# LCD_Board_v1_3.net
KiCad netlist of a schematic drawn in EAGLE
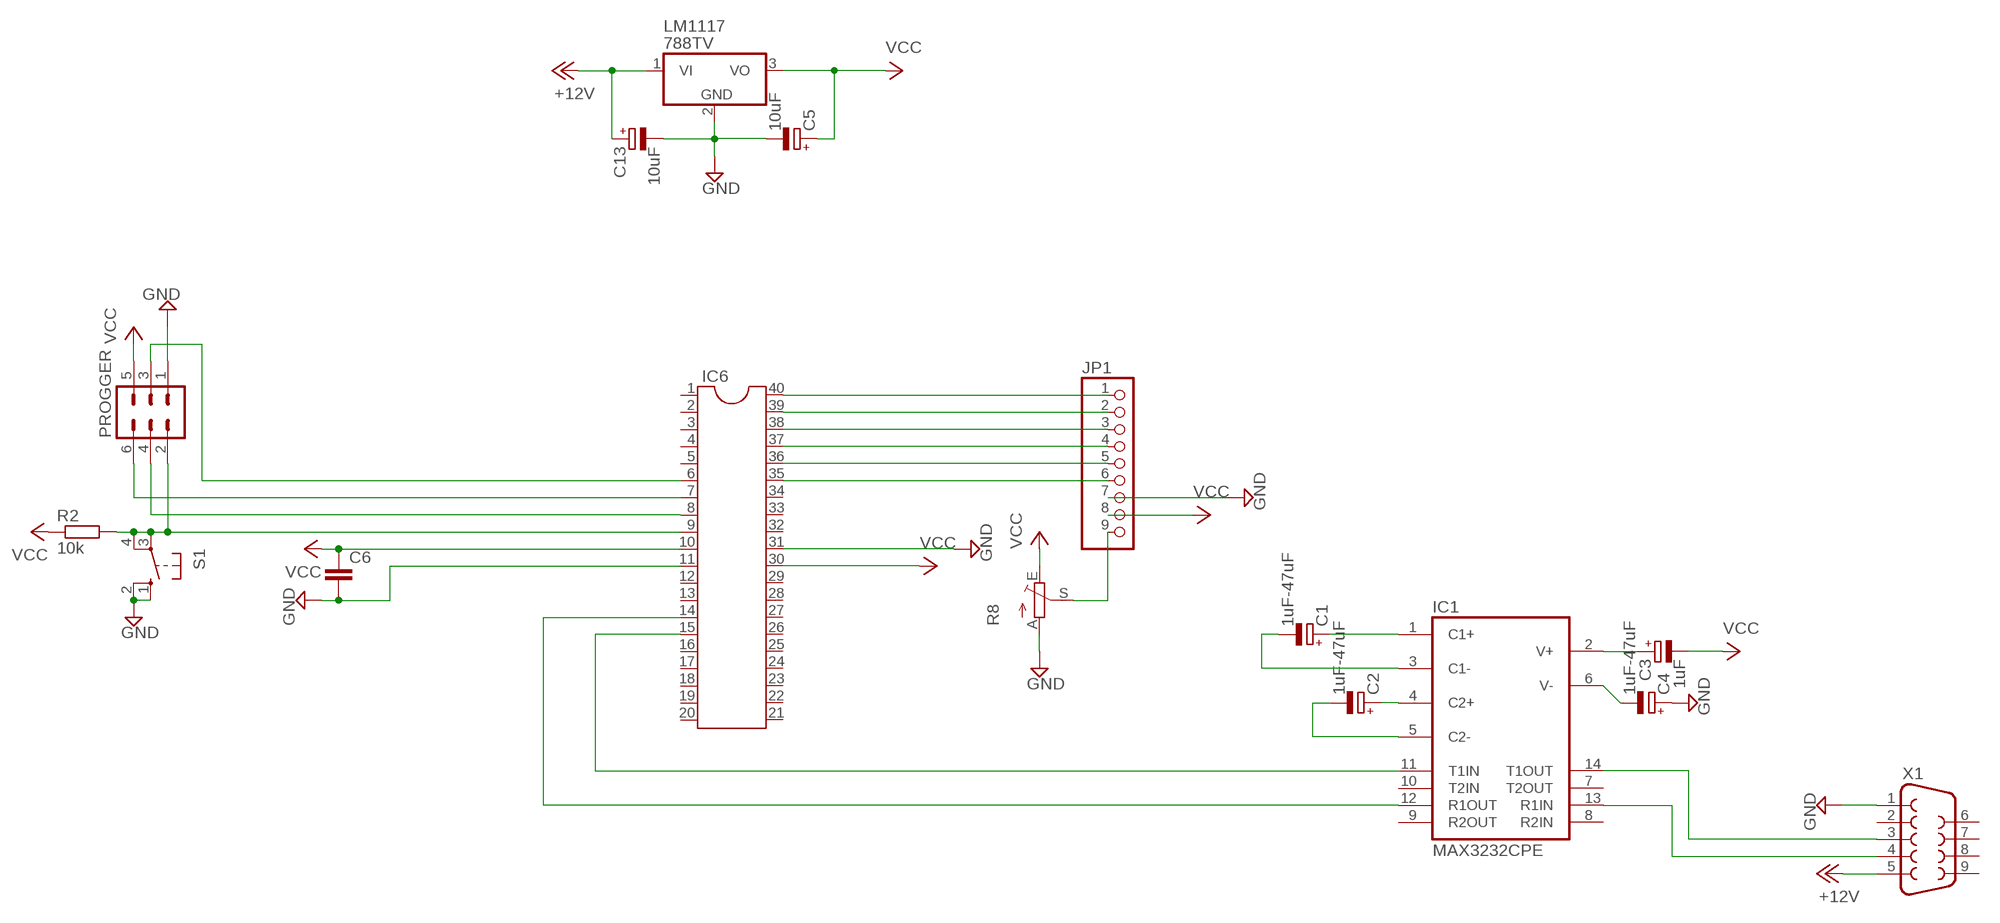
[diagram p0: schematic, sheet 1]
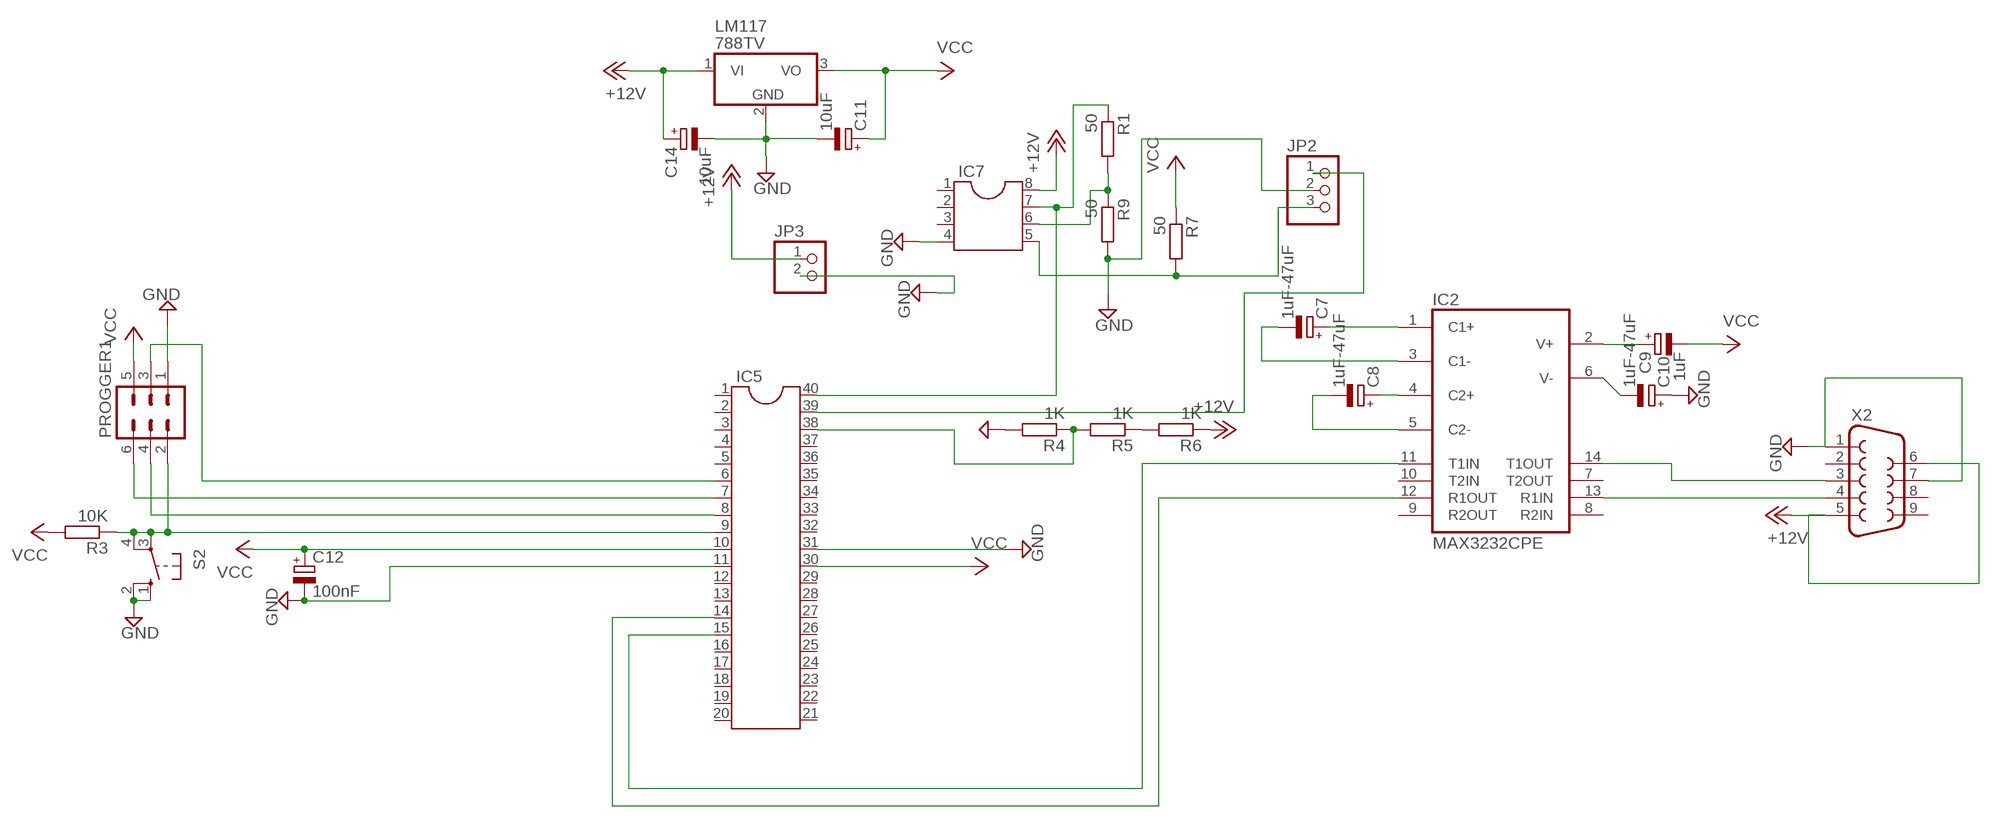
[diagram p1: schematic, sheet 2]

(export (version "E")
  (design (tool "Eeschema 10.0.6"))
  (components
    (comp (ref "C7")
      (value "1uF-47uF")
      (footprint "eagle-import:TT5D7")
      (libsource (lib "eagle-import") (part "CPOL-EUTT5D7"))
    )
    (comp (ref "C8")
      (value "1uF-47uF")
      (footprint "eagle-import:E2,5RE")
      (libsource (lib "eagle-import") (part "CPOL-EUE2.5-4V"))
    )
    (comp (ref "C9")
      (value "1uF")
      (footprint "eagle-import:TT5D7")
      (libsource (lib "eagle-import") (part "CPOL-EUTT5D7"))
    )
    (comp (ref "C10")
      (value "1uF-47uF")
      (footprint "eagle-import:E2,5RE")
      (libsource (lib "eagle-import") (part "CPOL-EUE2.5-4V"))
    )
    (comp (ref "C11")
      (value "10uF")
      (footprint "eagle-import:E2,5RE")
      (libsource (lib "eagle-import") (part "CPOL-EUE2.5-4V"))
    )
    (comp (ref "C12")
      (value "100nF")
      (footprint "eagle-import:E2,5RE")
      (libsource (lib "eagle-import") (part "CPOL-EUE2.5-4V"))
    )
    (comp (ref "C14")
      (value "10uF")
      (footprint "eagle-import:E2,5RE")
      (libsource (lib "eagle-import") (part "CPOL-EUE2.5-4V"))
    )
    (comp (ref "IC2")
      (value "MAX3232CPE")
      (footprint "eagle-import:DIL16")
      (fields (field (name "MF") "MAXIM") (field (name "MPN") "MAX3232CPE+"))
      (libsource (lib "eagle-import") (part "MAX3232PEC"))
    )
    (comp (ref "IC5")
      (value "DIL40")
      (footprint "eagle-import:DIL40")
      (libsource (lib "eagle-import") (part "DIL40"))
    )
    (comp (ref "IC7")
      (value "DIL8")
      (footprint "eagle-import:DIL08")
      (libsource (lib "eagle-import") (part "DIL8"))
    )
    (comp (ref "JP2")
      (value "PINHD-1X3")
      (footprint "eagle-import:1X03")
      (libsource (lib "eagle-import") (part "PINHD-1X3"))
    )
    (comp (ref "JP3")
      (value "PINHD-1X2")
      (footprint "eagle-import:1X02")
      (libsource (lib "eagle-import") (part "PINHD-1X2"))
    )
    (comp (ref "LM117")
      (value "788TV")
      (footprint "eagle-import:TO220V")
      (libsource (lib "eagle-import") (part "78TV8"))
    )
    (comp (ref "PROGGER1")
      (value "MA03-2")
      (footprint "eagle-import:MA03-2")
      (libsource (lib "eagle-import") (part "MA03-2"))
    )
    (comp (ref "R1")
      (value "50")
      (footprint "eagle-import:0204_7")
      (libsource (lib "eagle-import") (part "R-EU_0204/7"))
    )
    (comp (ref "R3")
      (value "10K")
      (footprint "eagle-import:0207_7")
      (libsource (lib "eagle-import") (part "R-EU_0207/7"))
    )
    (comp (ref "R4")
      (value "1K")
      (footprint "eagle-import:0204_7")
      (libsource (lib "eagle-import") (part "resistor_R-EU_0204/7"))
    )
    (comp (ref "R5")
      (value "1K")
      (footprint "eagle-import:0204_7")
      (libsource (lib "eagle-import") (part "resistor_R-EU_0204/7"))
    )
    (comp (ref "R6")
      (value "1K")
      (footprint "eagle-import:0204_7")
      (libsource (lib "eagle-import") (part "resistor_R-EU_0204/7"))
    )
    (comp (ref "R7")
      (value "50")
      (footprint "eagle-import:0204_5")
      (libsource (lib "eagle-import") (part "resistor_R-EU_0204/5"))
    )
    (comp (ref "R9")
      (value "50")
      (footprint "eagle-import:0204_7")
      (libsource (lib "eagle-import") (part "R-EU_0204/7"))
    )
    (comp (ref "S2")
      (value "10-XX")
      (footprint "eagle-import:B3F-10XX")
      (fields (field (name "MPN") "B3F-1000"))
      (libsource (lib "eagle-import") (part "10-XX"))
    )
    (comp (ref "X2")
      (value "F09H")
      (footprint "eagle-import:F09H")
      (libsource (lib "eagle-import") (part "F09H"))
    )
    (comp (ref "C1")
      (value "1uF-47uF")
      (footprint "eagle-import:TT5D7")
      (libsource (lib "eagle-import") (part "CPOL-EUTT5D7"))
    )
    (comp (ref "C2")
      (value "1uF-47uF")
      (footprint "eagle-import:E2,5RE")
      (libsource (lib "eagle-import") (part "CPOL-EUE2.5-4V"))
    )
    (comp (ref "C3")
      (value "1uF")
      (footprint "eagle-import:TT5D7")
      (libsource (lib "eagle-import") (part "CPOL-EUTT5D7"))
    )
    (comp (ref "C4")
      (value "1uF-47uF")
      (footprint "eagle-import:E2,5RE")
      (libsource (lib "eagle-import") (part "CPOL-EUE2.5-4V"))
    )
    (comp (ref "C5")
      (value "10uF")
      (footprint "eagle-import:E3,5-8")
      (libsource (lib "eagle-import") (part "CPOL-EUE3.5-8"))
    )
    (comp (ref "C6")
      (value "C-EU025-030X050")
      (footprint "eagle-import:C025-030X050")
      (libsource (lib "eagle-import") (part "C-EU025-030X050"))
    )
    (comp (ref "C13")
      (value "10uF")
      (footprint "eagle-import:E2,5RE")
      (libsource (lib "eagle-import") (part "CPOL-EUE2.5-4V"))
    )
    (comp (ref "IC1")
      (value "MAX3232CPE")
      (footprint "eagle-import:DIL16")
      (fields (field (name "MF") "MAXIM") (field (name "MPN") "MAX3232CPE+"))
      (libsource (lib "eagle-import") (part "MAX3232PEC"))
    )
    (comp (ref "IC6")
      (value "DIL40")
      (footprint "eagle-import:DIL40")
      (libsource (lib "eagle-import") (part "DIL40"))
    )
    (comp (ref "JP1")
      (value "PINHD-1X9")
      (footprint "eagle-import:1X09")
      (libsource (lib "eagle-import") (part "PINHD-1X9"))
    )
    (comp (ref "LM1117")
      (value "788TV")
      (footprint "eagle-import:TO220V")
      (libsource (lib "eagle-import") (part "78TV8"))
    )
    (comp (ref "PROGGER")
      (value "MA03-2")
      (footprint "eagle-import:MA03-2")
      (libsource (lib "eagle-import") (part "MA03-2"))
    )
    (comp (ref "R2")
      (value "10k")
      (footprint "eagle-import:0207_7")
      (libsource (lib "eagle-import") (part "R-EU_0207/7"))
    )
    (comp (ref "R8")
      (value "TRIM_EU-CA6V")
      (footprint "eagle-import:CA6V")
      (libsource (lib "eagle-import") (part "TRIM_EU-CA6V"))
    )
    (comp (ref "S1")
      (value "10-XX")
      (footprint "eagle-import:B3F-10XX")
      (fields (field (name "MPN") "B3F-1000"))
      (libsource (lib "eagle-import") (part "10-XX"))
    )
    (comp (ref "X1")
      (value "F09H")
      (footprint "eagle-import:F09H")
      (libsource (lib "eagle-import") (part "F09H"))
    )
  )
  (nets
    (net (code "1") (name "$N4") (class "Default")
      (node (ref "C10") (pin "+") (pinfunction "+_+") (pintype "passive"))
      (node (ref "C11") (pin "-") (pinfunction "-_-") (pintype "passive"))
      (node (ref "C12") (pin "-") (pinfunction "-_-") (pintype "passive"))
      (node (ref "C13") (pin "-") (pinfunction "-_-") (pintype "passive"))
      (node (ref "C14") (pin "-") (pinfunction "-_-") (pintype "passive"))
      (node (ref "C4") (pin "+") (pinfunction "+_+") (pintype "passive"))
      (node (ref "C5") (pin "-") (pinfunction "-_-") (pintype "passive"))
      (node (ref "C6") (pin "2") (pinfunction "2_2") (pintype "passive"))
      (node (ref "IC5") (pin "11") (pinfunction "11_11") (pintype "passive"))
      (node (ref "IC5") (pin "31") (pinfunction "31_31") (pintype "passive"))
      (node (ref "IC6") (pin "11") (pinfunction "11_11") (pintype "passive"))
      (node (ref "IC6") (pin "31") (pinfunction "31_31") (pintype "passive"))
      (node (ref "IC7") (pin "4") (pinfunction "4_4") (pintype "passive"))
      (node (ref "JP1") (pin "7") (pinfunction "7_7") (pintype "passive"))
      (node (ref "JP2") (pin "2") (pinfunction "2_2") (pintype "passive"))
      (node (ref "JP3") (pin "2") (pinfunction "2_2") (pintype "passive"))
      (node (ref "LM1117") (pin "2") (pinfunction "GND_2") (pintype "passive"))
      (node (ref "LM117") (pin "2") (pinfunction "GND_2") (pintype "passive"))
      (node (ref "PROGGER") (pin "1") (pinfunction "1_1") (pintype "passive"))
      (node (ref "PROGGER1") (pin "1") (pinfunction "1_1") (pintype "passive"))
      (node (ref "R4") (pin "2") (pinfunction "2_2") (pintype "passive"))
      (node (ref "R8") (pin "A") (pinfunction "A_A") (pintype "passive"))
      (node (ref "R9") (pin "2") (pinfunction "2_2") (pintype "passive"))
      (node (ref "S1") (pin "1") (pinfunction "S_1") (pintype "passive"))
      (node (ref "S1") (pin "2") (pinfunction "S1_2") (pintype "passive"))
      (node (ref "S2") (pin "1") (pinfunction "S_1") (pintype "passive"))
      (node (ref "S2") (pin "2") (pinfunction "S1_2") (pintype "passive"))
      (node (ref "X1") (pin "1") (pinfunction "1_1") (pintype "passive"))
      (node (ref "X2") (pin "1") (pinfunction "1_1") (pintype "passive"))
      (node (ref "X2") (pin "7") (pinfunction "7_7") (pintype "passive"))
    )
    (net (code "2") (name "+12V") (class "Default")
      (node (ref "C13") (pin "+") (pinfunction "+_+") (pintype "passive"))
      (node (ref "C14") (pin "+") (pinfunction "+_+") (pintype "passive"))
      (node (ref "IC7") (pin "8") (pinfunction "8_8") (pintype "passive"))
      (node (ref "JP3") (pin "1") (pinfunction "1_1") (pintype "passive"))
      (node (ref "LM1117") (pin "1") (pinfunction "VI_1") (pintype "input"))
      (node (ref "LM117") (pin "1") (pinfunction "VI_1") (pintype "input"))
      (node (ref "R6") (pin "1") (pinfunction "1_1") (pintype "passive"))
      (node (ref "X1") (pin "5") (pinfunction "5_5") (pintype "passive"))
      (node (ref "X2") (pin "5") (pinfunction "5_5") (pintype "passive"))
      (node (ref "X2") (pin "6") (pinfunction "6_6") (pintype "passive"))
    )
    (net (code "3") (name "Net-(IC1A-C1+)") (class "Default")
      (node (ref "C1") (pin "+") (pinfunction "+_+") (pintype "passive"))
      (node (ref "IC1") (pin "1") (pinfunction "C1+_1") (pintype "bidirectional"))
    )
    (net (code "4") (name "Net-(IC1A-C1-)") (class "Default")
      (node (ref "C1") (pin "-") (pinfunction "-_-") (pintype "passive"))
      (node (ref "IC1") (pin "3") (pinfunction "C1-_3") (pintype "bidirectional"))
    )
    (net (code "5") (name "Net-(IC1A-C2+)") (class "Default")
      (node (ref "C2") (pin "+") (pinfunction "+_+") (pintype "passive"))
      (node (ref "IC1") (pin "4") (pinfunction "C2+_4") (pintype "bidirectional"))
    )
    (net (code "6") (name "Net-(IC1A-C2-)") (class "Default")
      (node (ref "C2") (pin "-") (pinfunction "-_-") (pintype "passive"))
      (node (ref "IC1") (pin "5") (pinfunction "C2-_5") (pintype "bidirectional"))
    )
    (net (code "7") (name "Net-(IC1A-R1IN)") (class "Default")
      (node (ref "IC1") (pin "13") (pinfunction "R1IN_13") (pintype "input"))
      (node (ref "X1") (pin "4") (pinfunction "4_4") (pintype "passive"))
    )
    (net (code "8") (name "Net-(IC1A-R1OUT)") (class "Default")
      (node (ref "IC1") (pin "12") (pinfunction "R1OUT_12") (pintype "output"))
      (node (ref "IC6") (pin "14") (pinfunction "14_14") (pintype "passive"))
    )
    (net (code "9") (name "Net-(IC1A-T1IN)") (class "Default")
      (node (ref "IC1") (pin "11") (pinfunction "T1IN_11") (pintype "input"))
      (node (ref "IC6") (pin "15") (pinfunction "15_15") (pintype "passive"))
    )
    (net (code "10") (name "Net-(IC1A-T1OUT)") (class "Default")
      (node (ref "IC1") (pin "14") (pinfunction "T1OUT_14") (pintype "output"))
      (node (ref "X1") (pin "3") (pinfunction "3_3") (pintype "passive"))
    )
    (net (code "11") (name "Net-(IC1A-V+)") (class "Default")
      (node (ref "C3") (pin "+") (pinfunction "+_+") (pintype "passive"))
      (node (ref "IC1") (pin "2") (pinfunction "V+_2") (pintype "bidirectional"))
    )
    (net (code "12") (name "Net-(IC1A-V-)") (class "Default")
      (node (ref "C4") (pin "-") (pinfunction "-_-") (pintype "passive"))
      (node (ref "IC1") (pin "6") (pinfunction "V-_6") (pintype "bidirectional"))
    )
    (net (code "13") (name "Net-(IC2A-C1+)") (class "Default")
      (node (ref "C7") (pin "+") (pinfunction "+_+") (pintype "passive"))
      (node (ref "IC2") (pin "1") (pinfunction "C1+_1") (pintype "bidirectional"))
    )
    (net (code "14") (name "Net-(IC2A-C1-)") (class "Default")
      (node (ref "C7") (pin "-") (pinfunction "-_-") (pintype "passive"))
      (node (ref "IC2") (pin "3") (pinfunction "C1-_3") (pintype "bidirectional"))
    )
    (net (code "15") (name "Net-(IC2A-C2+)") (class "Default")
      (node (ref "C8") (pin "+") (pinfunction "+_+") (pintype "passive"))
      (node (ref "IC2") (pin "4") (pinfunction "C2+_4") (pintype "bidirectional"))
    )
    (net (code "16") (name "Net-(IC2A-C2-)") (class "Default")
      (node (ref "C8") (pin "-") (pinfunction "-_-") (pintype "passive"))
      (node (ref "IC2") (pin "5") (pinfunction "C2-_5") (pintype "bidirectional"))
    )
    (net (code "17") (name "Net-(IC2A-R1IN)") (class "Default")
      (node (ref "IC2") (pin "13") (pinfunction "R1IN_13") (pintype "input"))
      (node (ref "X2") (pin "4") (pinfunction "4_4") (pintype "passive"))
    )
    (net (code "18") (name "Net-(IC2A-R1OUT)") (class "Default")
      (node (ref "IC2") (pin "12") (pinfunction "R1OUT_12") (pintype "output"))
      (node (ref "IC5") (pin "14") (pinfunction "14_14") (pintype "passive"))
    )
    (net (code "19") (name "Net-(IC2A-T1IN)") (class "Default")
      (node (ref "IC2") (pin "11") (pinfunction "T1IN_11") (pintype "input"))
      (node (ref "IC5") (pin "15") (pinfunction "15_15") (pintype "passive"))
    )
    (net (code "20") (name "Net-(IC2A-T1OUT)") (class "Default")
      (node (ref "IC2") (pin "14") (pinfunction "T1OUT_14") (pintype "output"))
      (node (ref "X2") (pin "3") (pinfunction "3_3") (pintype "passive"))
    )
    (net (code "21") (name "Net-(IC2A-V+)") (class "Default")
      (node (ref "C9") (pin "+") (pinfunction "+_+") (pintype "passive"))
      (node (ref "IC2") (pin "2") (pinfunction "V+_2") (pintype "bidirectional"))
    )
    (net (code "22") (name "Net-(IC2A-V-)") (class "Default")
      (node (ref "C10") (pin "-") (pinfunction "-_-") (pintype "passive"))
      (node (ref "IC2") (pin "6") (pinfunction "V-_6") (pintype "bidirectional"))
    )
    (net (code "23") (name "Net-(IC5-Pad6)") (class "Default")
      (node (ref "IC5") (pin "6") (pinfunction "6_6") (pintype "passive"))
      (node (ref "PROGGER1") (pin "3") (pinfunction "3_3") (pintype "passive"))
    )
    (net (code "24") (name "Net-(IC5-Pad7)") (class "Default")
      (node (ref "IC5") (pin "7") (pinfunction "7_7") (pintype "passive"))
      (node (ref "PROGGER1") (pin "6") (pinfunction "6_6") (pintype "passive"))
    )
    (net (code "25") (name "Net-(IC5-Pad8)") (class "Default")
      (node (ref "IC5") (pin "8") (pinfunction "8_8") (pintype "passive"))
      (node (ref "PROGGER1") (pin "4") (pinfunction "4_4") (pintype "passive"))
    )
    (net (code "26") (name "Net-(IC5-Pad38)") (class "Default")
      (node (ref "IC5") (pin "38") (pinfunction "38_38") (pintype "passive"))
      (node (ref "R4") (pin "1") (pinfunction "1_1") (pintype "passive"))
      (node (ref "R5") (pin "2") (pinfunction "2_2") (pintype "passive"))
    )
    (net (code "27") (name "Net-(IC5-Pad39)") (class "Default")
      (node (ref "IC5") (pin "39") (pinfunction "39_39") (pintype "passive"))
      (node (ref "JP2") (pin "1") (pinfunction "1_1") (pintype "passive"))
    )
    (net (code "28") (name "Net-(IC5-Pad40)") (class "Default")
      (node (ref "IC5") (pin "40") (pinfunction "40_40") (pintype "passive"))
      (node (ref "IC7") (pin "7") (pinfunction "7_7") (pintype "passive"))
      (node (ref "R1") (pin "1") (pinfunction "1_1") (pintype "passive"))
    )
    (net (code "29") (name "Net-(IC6-Pad6)") (class "Default")
      (node (ref "IC6") (pin "6") (pinfunction "6_6") (pintype "passive"))
      (node (ref "PROGGER") (pin "3") (pinfunction "3_3") (pintype "passive"))
    )
    (net (code "30") (name "Net-(IC6-Pad7)") (class "Default")
      (node (ref "IC6") (pin "7") (pinfunction "7_7") (pintype "passive"))
      (node (ref "PROGGER") (pin "6") (pinfunction "6_6") (pintype "passive"))
    )
    (net (code "31") (name "Net-(IC6-Pad8)") (class "Default")
      (node (ref "IC6") (pin "8") (pinfunction "8_8") (pintype "passive"))
      (node (ref "PROGGER") (pin "4") (pinfunction "4_4") (pintype "passive"))
    )
    (net (code "32") (name "Net-(IC6-Pad35)") (class "Default")
      (node (ref "IC6") (pin "35") (pinfunction "35_35") (pintype "passive"))
      (node (ref "JP1") (pin "6") (pinfunction "6_6") (pintype "passive"))
    )
    (net (code "33") (name "Net-(IC6-Pad36)") (class "Default")
      (node (ref "IC6") (pin "36") (pinfunction "36_36") (pintype "passive"))
      (node (ref "JP1") (pin "5") (pinfunction "5_5") (pintype "passive"))
    )
    (net (code "34") (name "Net-(IC6-Pad37)") (class "Default")
      (node (ref "IC6") (pin "37") (pinfunction "37_37") (pintype "passive"))
      (node (ref "JP1") (pin "4") (pinfunction "4_4") (pintype "passive"))
    )
    (net (code "35") (name "Net-(IC6-Pad38)") (class "Default")
      (node (ref "IC6") (pin "38") (pinfunction "38_38") (pintype "passive"))
      (node (ref "JP1") (pin "3") (pinfunction "3_3") (pintype "passive"))
    )
    (net (code "36") (name "Net-(IC6-Pad39)") (class "Default")
      (node (ref "IC6") (pin "39") (pinfunction "39_39") (pintype "passive"))
      (node (ref "JP1") (pin "2") (pinfunction "2_2") (pintype "passive"))
    )
    (net (code "37") (name "Net-(IC6-Pad40)") (class "Default")
      (node (ref "IC6") (pin "40") (pinfunction "40_40") (pintype "passive"))
      (node (ref "JP1") (pin "1") (pinfunction "1_1") (pintype "passive"))
    )
    (net (code "38") (name "Net-(IC7-Pad5)") (class "Default")
      (node (ref "IC7") (pin "5") (pinfunction "5_5") (pintype "passive"))
      (node (ref "JP2") (pin "3") (pinfunction "3_3") (pintype "passive"))
      (node (ref "R7") (pin "2") (pinfunction "2_2") (pintype "passive"))
    )
    (net (code "39") (name "Net-(IC7-Pad6)") (class "Default")
      (node (ref "IC7") (pin "6") (pinfunction "6_6") (pintype "passive"))
      (node (ref "R1") (pin "2") (pinfunction "2_2") (pintype "passive"))
      (node (ref "R9") (pin "1") (pinfunction "1_1") (pintype "passive"))
    )
    (net (code "40") (name "Net-(JP1-Pad9)") (class "Default")
      (node (ref "JP1") (pin "9") (pinfunction "9_9") (pintype "passive"))
      (node (ref "R8") (pin "S") (pinfunction "S_S") (pintype "passive"))
    )
    (net (code "41") (name "Net-(R5-Pad1)") (class "Default")
      (node (ref "R5") (pin "1") (pinfunction "1_1") (pintype "passive"))
      (node (ref "R6") (pin "2") (pinfunction "2_2") (pintype "passive"))
    )
    (net (code "42") (name "Net-(S1-P)") (class "Default")
      (node (ref "IC6") (pin "9") (pinfunction "9_9") (pintype "passive"))
      (node (ref "PROGGER") (pin "2") (pinfunction "2_2") (pintype "passive"))
      (node (ref "R2") (pin "2") (pinfunction "2_2") (pintype "passive"))
      (node (ref "S1") (pin "3") (pinfunction "P_3") (pintype "passive"))
      (node (ref "S1") (pin "4") (pinfunction "P1_4") (pintype "passive"))
    )
    (net (code "43") (name "Net-(S2-P)") (class "Default")
      (node (ref "IC5") (pin "9") (pinfunction "9_9") (pintype "passive"))
      (node (ref "PROGGER1") (pin "2") (pinfunction "2_2") (pintype "passive"))
      (node (ref "R3") (pin "1") (pinfunction "1_1") (pintype "passive"))
      (node (ref "S2") (pin "3") (pinfunction "P_3") (pintype "passive"))
      (node (ref "S2") (pin "4") (pinfunction "P1_4") (pintype "passive"))
    )
    (net (code "44") (name "VCC") (class "Default")
      (node (ref "C11") (pin "+") (pinfunction "+_+") (pintype "passive"))
      (node (ref "C12") (pin "+") (pinfunction "+_+") (pintype "passive"))
      (node (ref "C3") (pin "-") (pinfunction "-_-") (pintype "passive"))
      (node (ref "C5") (pin "+") (pinfunction "+_+") (pintype "passive"))
      (node (ref "C6") (pin "1") (pinfunction "1_1") (pintype "passive"))
      (node (ref "C9") (pin "-") (pinfunction "-_-") (pintype "passive"))
      (node (ref "IC5") (pin "10") (pinfunction "10_10") (pintype "passive"))
      (node (ref "IC5") (pin "30") (pinfunction "30_30") (pintype "passive"))
      (node (ref "IC6") (pin "10") (pinfunction "10_10") (pintype "passive"))
      (node (ref "IC6") (pin "30") (pinfunction "30_30") (pintype "passive"))
      (node (ref "JP1") (pin "8") (pinfunction "8_8") (pintype "passive"))
      (node (ref "LM1117") (pin "3") (pinfunction "VO_3") (pintype "passive"))
      (node (ref "LM117") (pin "3") (pinfunction "VO_3") (pintype "passive"))
      (node (ref "PROGGER") (pin "5") (pinfunction "5_5") (pintype "passive"))
      (node (ref "PROGGER1") (pin "5") (pinfunction "5_5") (pintype "passive"))
      (node (ref "R2") (pin "1") (pinfunction "1_1") (pintype "passive"))
      (node (ref "R3") (pin "2") (pinfunction "2_2") (pintype "passive"))
      (node (ref "R7") (pin "1") (pinfunction "1_1") (pintype "passive"))
      (node (ref "R8") (pin "E") (pinfunction "E_E") (pintype "passive"))
    )
    (net (code "45") (name "unconnected-(IC1A-R2IN-Pad8)") (class "Default")
      (node (ref "IC1") (pin "8") (pinfunction "R2IN_8") (pintype "input"))
    )
    (net (code "46") (name "unconnected-(IC1A-R2OUT-Pad9)") (class "Default")
      (node (ref "IC1") (pin "9") (pinfunction "R2OUT_9") (pintype "output"))
    )
    (net (code "47") (name "unconnected-(IC1A-T2IN-Pad10)") (class "Default")
      (node (ref "IC1") (pin "10") (pinfunction "T2IN_10") (pintype "input"))
    )
    (net (code "48") (name "unconnected-(IC1A-T2OUT-Pad7)") (class "Default")
      (node (ref "IC1") (pin "7") (pinfunction "T2OUT_7") (pintype "output"))
    )
    (net (code "49") (name "unconnected-(IC2A-R2IN-Pad8)") (class "Default")
      (node (ref "IC2") (pin "8") (pinfunction "R2IN_8") (pintype "input"))
    )
    (net (code "50") (name "unconnected-(IC2A-R2OUT-Pad9)") (class "Default")
      (node (ref "IC2") (pin "9") (pinfunction "R2OUT_9") (pintype "output"))
    )
    (net (code "51") (name "unconnected-(IC2A-T2IN-Pad10)") (class "Default")
      (node (ref "IC2") (pin "10") (pinfunction "T2IN_10") (pintype "input"))
    )
    (net (code "52") (name "unconnected-(IC2A-T2OUT-Pad7)") (class "Default")
      (node (ref "IC2") (pin "7") (pinfunction "T2OUT_7") (pintype "output"))
    )
    (net (code "53") (name "unconnected-(IC5-Pad1)") (class "Default")
      (node (ref "IC5") (pin "1") (pinfunction "1_1") (pintype "passive"))
    )
    (net (code "54") (name "unconnected-(IC5-Pad2)") (class "Default")
      (node (ref "IC5") (pin "2") (pinfunction "2_2") (pintype "passive"))
    )
    (net (code "55") (name "unconnected-(IC5-Pad3)") (class "Default")
      (node (ref "IC5") (pin "3") (pinfunction "3_3") (pintype "passive"))
    )
    (net (code "56") (name "unconnected-(IC5-Pad4)") (class "Default")
      (node (ref "IC5") (pin "4") (pinfunction "4_4") (pintype "passive"))
    )
    (net (code "57") (name "unconnected-(IC5-Pad5)") (class "Default")
      (node (ref "IC5") (pin "5") (pinfunction "5_5") (pintype "passive"))
    )
    (net (code "58") (name "unconnected-(IC5-Pad12)") (class "Default")
      (node (ref "IC5") (pin "12") (pinfunction "12_12") (pintype "passive"))
    )
    (net (code "59") (name "unconnected-(IC5-Pad13)") (class "Default")
      (node (ref "IC5") (pin "13") (pinfunction "13_13") (pintype "passive"))
    )
    (net (code "60") (name "unconnected-(IC5-Pad16)") (class "Default")
      (node (ref "IC5") (pin "16") (pinfunction "16_16") (pintype "passive"))
    )
    (net (code "61") (name "unconnected-(IC5-Pad17)") (class "Default")
      (node (ref "IC5") (pin "17") (pinfunction "17_17") (pintype "passive"))
    )
    (net (code "62") (name "unconnected-(IC5-Pad18)") (class "Default")
      (node (ref "IC5") (pin "18") (pinfunction "18_18") (pintype "passive"))
    )
    (net (code "63") (name "unconnected-(IC5-Pad19)") (class "Default")
      (node (ref "IC5") (pin "19") (pinfunction "19_19") (pintype "passive"))
    )
    (net (code "64") (name "unconnected-(IC5-Pad20)") (class "Default")
      (node (ref "IC5") (pin "20") (pinfunction "20_20") (pintype "passive"))
    )
    (net (code "65") (name "unconnected-(IC5-Pad21)") (class "Default")
      (node (ref "IC5") (pin "21") (pinfunction "21_21") (pintype "passive"))
    )
    (net (code "66") (name "unconnected-(IC5-Pad22)") (class "Default")
      (node (ref "IC5") (pin "22") (pinfunction "22_22") (pintype "passive"))
    )
    (net (code "67") (name "unconnected-(IC5-Pad23)") (class "Default")
      (node (ref "IC5") (pin "23") (pinfunction "23_23") (pintype "passive"))
    )
    (net (code "68") (name "unconnected-(IC5-Pad24)") (class "Default")
      (node (ref "IC5") (pin "24") (pinfunction "24_24") (pintype "passive"))
    )
    (net (code "69") (name "unconnected-(IC5-Pad25)") (class "Default")
      (node (ref "IC5") (pin "25") (pinfunction "25_25") (pintype "passive"))
    )
    (net (code "70") (name "unconnected-(IC5-Pad26)") (class "Default")
      (node (ref "IC5") (pin "26") (pinfunction "26_26") (pintype "passive"))
    )
    (net (code "71") (name "unconnected-(IC5-Pad27)") (class "Default")
      (node (ref "IC5") (pin "27") (pinfunction "27_27") (pintype "passive"))
    )
    (net (code "72") (name "unconnected-(IC5-Pad28)") (class "Default")
      (node (ref "IC5") (pin "28") (pinfunction "28_28") (pintype "passive"))
    )
    (net (code "73") (name "unconnected-(IC5-Pad29)") (class "Default")
      (node (ref "IC5") (pin "29") (pinfunction "29_29") (pintype "passive"))
    )
    (net (code "74") (name "unconnected-(IC5-Pad32)") (class "Default")
      (node (ref "IC5") (pin "32") (pinfunction "32_32") (pintype "passive"))
    )
    (net (code "75") (name "unconnected-(IC5-Pad33)") (class "Default")
      (node (ref "IC5") (pin "33") (pinfunction "33_33") (pintype "passive"))
    )
    (net (code "76") (name "unconnected-(IC5-Pad34)") (class "Default")
      (node (ref "IC5") (pin "34") (pinfunction "34_34") (pintype "passive"))
    )
    (net (code "77") (name "unconnected-(IC5-Pad35)") (class "Default")
      (node (ref "IC5") (pin "35") (pinfunction "35_35") (pintype "passive"))
    )
    (net (code "78") (name "unconnected-(IC5-Pad36)") (class "Default")
      (node (ref "IC5") (pin "36") (pinfunction "36_36") (pintype "passive"))
    )
    (net (code "79") (name "unconnected-(IC5-Pad37)") (class "Default")
      (node (ref "IC5") (pin "37") (pinfunction "37_37") (pintype "passive"))
    )
    (net (code "80") (name "unconnected-(IC6-Pad1)") (class "Default")
      (node (ref "IC6") (pin "1") (pinfunction "1_1") (pintype "passive"))
    )
    (net (code "81") (name "unconnected-(IC6-Pad2)") (class "Default")
      (node (ref "IC6") (pin "2") (pinfunction "2_2") (pintype "passive"))
    )
    (net (code "82") (name "unconnected-(IC6-Pad3)") (class "Default")
      (node (ref "IC6") (pin "3") (pinfunction "3_3") (pintype "passive"))
    )
    (net (code "83") (name "unconnected-(IC6-Pad4)") (class "Default")
      (node (ref "IC6") (pin "4") (pinfunction "4_4") (pintype "passive"))
    )
    (net (code "84") (name "unconnected-(IC6-Pad5)") (class "Default")
      (node (ref "IC6") (pin "5") (pinfunction "5_5") (pintype "passive"))
    )
    (net (code "85") (name "unconnected-(IC6-Pad12)") (class "Default")
      (node (ref "IC6") (pin "12") (pinfunction "12_12") (pintype "passive"))
    )
    (net (code "86") (name "unconnected-(IC6-Pad13)") (class "Default")
      (node (ref "IC6") (pin "13") (pinfunction "13_13") (pintype "passive"))
    )
    (net (code "87") (name "unconnected-(IC6-Pad16)") (class "Default")
      (node (ref "IC6") (pin "16") (pinfunction "16_16") (pintype "passive"))
    )
    (net (code "88") (name "unconnected-(IC6-Pad17)") (class "Default")
      (node (ref "IC6") (pin "17") (pinfunction "17_17") (pintype "passive"))
    )
    (net (code "89") (name "unconnected-(IC6-Pad18)") (class "Default")
      (node (ref "IC6") (pin "18") (pinfunction "18_18") (pintype "passive"))
    )
    (net (code "90") (name "unconnected-(IC6-Pad19)") (class "Default")
      (node (ref "IC6") (pin "19") (pinfunction "19_19") (pintype "passive"))
    )
    (net (code "91") (name "unconnected-(IC6-Pad20)") (class "Default")
      (node (ref "IC6") (pin "20") (pinfunction "20_20") (pintype "passive"))
    )
    (net (code "92") (name "unconnected-(IC6-Pad21)") (class "Default")
      (node (ref "IC6") (pin "21") (pinfunction "21_21") (pintype "passive"))
    )
    (net (code "93") (name "unconnected-(IC6-Pad22)") (class "Default")
      (node (ref "IC6") (pin "22") (pinfunction "22_22") (pintype "passive"))
    )
    (net (code "94") (name "unconnected-(IC6-Pad23)") (class "Default")
      (node (ref "IC6") (pin "23") (pinfunction "23_23") (pintype "passive"))
    )
    (net (code "95") (name "unconnected-(IC6-Pad24)") (class "Default")
      (node (ref "IC6") (pin "24") (pinfunction "24_24") (pintype "passive"))
    )
    (net (code "96") (name "unconnected-(IC6-Pad25)") (class "Default")
      (node (ref "IC6") (pin "25") (pinfunction "25_25") (pintype "passive"))
    )
    (net (code "97") (name "unconnected-(IC6-Pad26)") (class "Default")
      (node (ref "IC6") (pin "26") (pinfunction "26_26") (pintype "passive"))
    )
    (net (code "98") (name "unconnected-(IC6-Pad27)") (class "Default")
      (node (ref "IC6") (pin "27") (pinfunction "27_27") (pintype "passive"))
    )
    (net (code "99") (name "unconnected-(IC6-Pad28)") (class "Default")
      (node (ref "IC6") (pin "28") (pinfunction "28_28") (pintype "passive"))
    )
    (net (code "100") (name "unconnected-(IC6-Pad29)") (class "Default")
      (node (ref "IC6") (pin "29") (pinfunction "29_29") (pintype "passive"))
    )
    (net (code "101") (name "unconnected-(IC6-Pad32)") (class "Default")
      (node (ref "IC6") (pin "32") (pinfunction "32_32") (pintype "passive"))
    )
    (net (code "102") (name "unconnected-(IC6-Pad33)") (class "Default")
      (node (ref "IC6") (pin "33") (pinfunction "33_33") (pintype "passive"))
    )
    (net (code "103") (name "unconnected-(IC6-Pad34)") (class "Default")
      (node (ref "IC6") (pin "34") (pinfunction "34_34") (pintype "passive"))
    )
    (net (code "104") (name "unconnected-(IC7-Pad1)") (class "Default")
      (node (ref "IC7") (pin "1") (pinfunction "1_1") (pintype "passive"))
    )
    (net (code "105") (name "unconnected-(IC7-Pad2)") (class "Default")
      (node (ref "IC7") (pin "2") (pinfunction "2_2") (pintype "passive"))
    )
    (net (code "106") (name "unconnected-(IC7-Pad3)") (class "Default")
      (node (ref "IC7") (pin "3") (pinfunction "3_3") (pintype "passive"))
    )
    (net (code "107") (name "unconnected-(X1-Pad2)") (class "Default")
      (node (ref "X1") (pin "2") (pinfunction "2_2") (pintype "passive"))
    )
    (net (code "108") (name "unconnected-(X1-Pad6)") (class "Default")
      (node (ref "X1") (pin "6") (pinfunction "6_6") (pintype "passive"))
    )
    (net (code "109") (name "unconnected-(X1-Pad7)") (class "Default")
      (node (ref "X1") (pin "7") (pinfunction "7_7") (pintype "passive"))
    )
    (net (code "110") (name "unconnected-(X1-Pad8)") (class "Default")
      (node (ref "X1") (pin "8") (pinfunction "8_8") (pintype "passive"))
    )
    (net (code "111") (name "unconnected-(X1-Pad9)") (class "Default")
      (node (ref "X1") (pin "9") (pinfunction "9_9") (pintype "passive"))
    )
    (net (code "112") (name "unconnected-(X2-Pad2)") (class "Default")
      (node (ref "X2") (pin "2") (pinfunction "2_2") (pintype "passive"))
    )
    (net (code "113") (name "unconnected-(X2-Pad8)") (class "Default")
      (node (ref "X2") (pin "8") (pinfunction "8_8") (pintype "passive"))
    )
    (net (code "114") (name "unconnected-(X2-Pad9)") (class "Default")
      (node (ref "X2") (pin "9") (pinfunction "9_9") (pintype "passive"))
    )
  )
)
